# TOP.net
KiCad netlist of a schematic drawn in Altium Designer
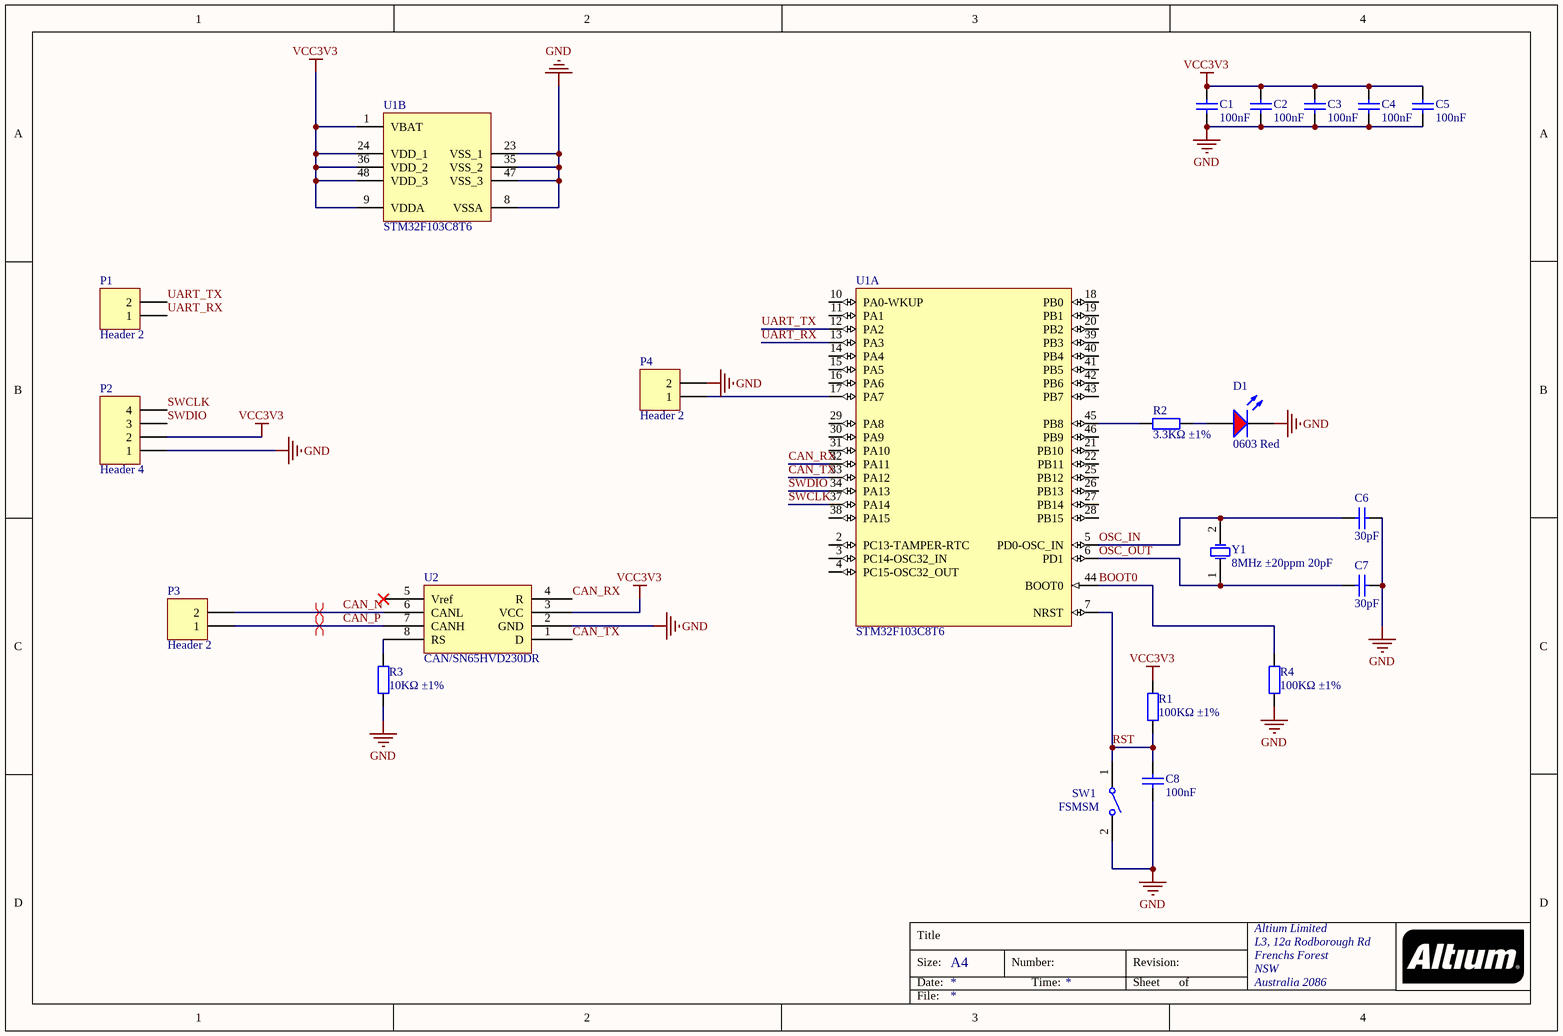
[diagram p0: TOP.SchDoc]

(export (version "E")
  (design (tool "Eeschema 10.0.6"))
  (components
    (comp (ref "C1")
      (value "100nF")
      (footprint "0402_C")
      (description "Chip capacitors")
      (fields
        (field (name "MANUFACTURER") "Samsung Electro-Mechanics")
        (field (name "PARTNUMBER") "CL05B104KO5NNNC")
      )
      (libsource (lib "Miscellaneous Devices LC") (part "0402 100nF (104) 10% 16V"))
    )
    (comp (ref "C2")
      (value "100nF")
      (footprint "0402_C")
      (description "Chip capacitors")
      (fields
        (field (name "MANUFACTURER") "Samsung Electro-Mechanics")
        (field (name "PARTNUMBER") "CL05B104KO5NNNC")
      )
      (libsource (lib "Miscellaneous Devices LC") (part "0402 100nF (104) 10% 16V"))
    )
    (comp (ref "C3")
      (value "100nF")
      (footprint "0402_C")
      (description "Chip capacitors")
      (fields
        (field (name "MANUFACTURER") "Samsung Electro-Mechanics")
        (field (name "PARTNUMBER") "CL05B104KO5NNNC")
      )
      (libsource (lib "Miscellaneous Devices LC") (part "0402 100nF (104) 10% 16V"))
    )
    (comp (ref "C4")
      (value "100nF")
      (footprint "0402_C")
      (description "Chip capacitors")
      (fields
        (field (name "MANUFACTURER") "Samsung Electro-Mechanics")
        (field (name "PARTNUMBER") "CL05B104KO5NNNC")
      )
      (libsource (lib "Miscellaneous Devices LC") (part "0402 100nF (104) 10% 16V"))
    )
    (comp (ref "C5")
      (value "100nF")
      (footprint "0402_C")
      (description "Chip capacitors")
      (fields
        (field (name "MANUFACTURER") "Samsung Electro-Mechanics")
        (field (name "PARTNUMBER") "CL05B104KO5NNNC")
      )
      (libsource (lib "Miscellaneous Devices LC") (part "0402 100nF (104) 10% 16V"))
    )
    (comp (ref "C6")
      (value "30pF")
      (footprint "0402_C")
      (description "Chip capacitors")
      (fields
        (field (name "MANUFACTURER") "Guangdong Fenghua Advanced Tech")
        (field (name "PARTNUMBER") "0402CG300J500NT")
      )
      (libsource (lib "Miscellaneous Devices LC") (part "0402 30pF (300) 5% 50V"))
    )
    (comp (ref "C7")
      (value "30pF")
      (footprint "0402_C")
      (description "Chip capacitors")
      (fields
        (field (name "MANUFACTURER") "Guangdong Fenghua Advanced Tech")
        (field (name "PARTNUMBER") "0402CG300J500NT")
      )
      (libsource (lib "Miscellaneous Devices LC") (part "0402 30pF (300) 5% 50V"))
    )
    (comp (ref "C8")
      (value "100nF")
      (footprint "0402_C")
      (description "Chip capacitors")
      (fields
        (field (name "MANUFACTURER") "Samsung Electro-Mechanics")
        (field (name "PARTNUMBER") "CL05B104KO5NNNC")
      )
      (libsource (lib "Miscellaneous Devices LC") (part "0402 100nF (104) 10% 16V"))
    )
    (comp (ref "D1")
      (value "0603 Red")
      (footprint "0603_LED_S1")
      (description "LED")
      (libsource (lib "Miscellaneous Devices LC") (part "0603 LED Red"))
    )
    (comp (ref "P1")
      (value "Header 2")
      (footprint "HDR1X2")
      (description "Header, 2-Pin")
      (fields (field (name "PUBLISHER") "Altium Limited"))
      (libsource (lib "Miscellaneous Connectors") (part "Header 2"))
    )
    (comp (ref "P2")
      (value "Header 4")
      (footprint "HDR1X4")
      (description "Header, 4-Pin")
      (fields (field (name "PUBLISHER") "Altium Limited"))
      (libsource (lib "Miscellaneous Connectors") (part "Header 4"))
    )
    (comp (ref "P3")
      (value "Header 2")
      (footprint "HDR1X2")
      (description "Header, 2-Pin")
      (fields (field (name "PUBLISHER") "Altium Limited"))
      (libsource (lib "Miscellaneous Connectors") (part "Header 2"))
    )
    (comp (ref "P4")
      (value "Header 2")
      (footprint "HDR1X2")
      (description "Header, 2-Pin")
      (fields (field (name "PUBLISHER") "Altium Limited"))
      (libsource (lib "Miscellaneous Connectors") (part "Header 2"))
    )
    (comp (ref "R1")
      (value "100KΩ ±1%")
      (footprint "0402_R")
      (description "Chip resistor")
      (fields (field (name "MANUFACTURER") "Uniroyal Elec") (field (name "PARTNUMBER") "0402WGF1003TCE"))
      (libsource (lib "Miscellaneous Devices LC") (part "0402 100K (1003) 1%"))
    )
    (comp (ref "R2")
      (value "3.3KΩ ±1%")
      (footprint "0402_R")
      (description "Chip resistor")
      (fields (field (name "MANUFACTURER") "Uniroyal Elec") (field (name "PARTNUMBER") "0402WGF3301TCE"))
      (libsource (lib "Miscellaneous Devices LC") (part "0402 3.3K (3301) 1%"))
    )
    (comp (ref "R3")
      (value "10KΩ ±1%")
      (footprint "0402_R")
      (description "Chip resistor")
      (fields (field (name "MANUFACTURER") "Uniroyal Elec") (field (name "PARTNUMBER") "0402WGF1002TCE"))
      (libsource (lib "Miscellaneous Devices LC") (part "0402 10K (1002) 1%"))
    )
    (comp (ref "R4")
      (value "100KΩ ±1%")
      (footprint "0402_R")
      (description "Chip resistor")
      (fields (field (name "MANUFACTURER") "Uniroyal Elec") (field (name "PARTNUMBER") "0402WGF1003TCE"))
      (libsource (lib "Miscellaneous Devices LC") (part "0402 100K (1003) 1%"))
    )
    (comp (ref "SW1")
      (value "FSMSM")
      (footprint "TECO-FSMSM-2_V")
      (description "FSMSM Push Button Switch, 50 mA, -35 to 85 degC, 2-Pin SMD, RoHS, Bulk")
      (fields (field (name "MANUFACTURER") "TE Connectivity"))
      (libsource (lib "Altium Content Vault") (part "SW-SPST-2_C"))
    )
    (comp (ref "U1")
      (value "STM32F103C8T6")
      (footprint "LQFP-48_7x7x05P")
      (description "ARM")
      (libsource (lib "Miscellaneous Devices LC") (part "STM32F103C8T6"))
    )
    (comp (ref "U2")
      (value "CAN/SN65HVD230DR")
      (footprint "SOIC-8_150mil")
      (description "CAN")
      (libsource (lib "Miscellaneous Devices LC") (part "CAN/SN65HVD230DR_[C12084]"))
    )
    (comp (ref "Y1")
      (value "8MHz ±20ppm 20pF")
      (footprint "SMD-5032_2P")
      (description "贴片晶振")
      (libsource (lib "Miscellaneous Devices LC") (part "SMD-5032_2P 8MHz 20ppm 20pF"))
    )
  )
  (nets
    (net (code "1") (name "/BOOT0") (class "Default")
      (node (ref "R4") (pin "2") (pinfunction "2_2") (pintype "passive"))
      (node (ref "U1") (pin "44") (pinfunction "BOOT0_44") (pintype "input"))
    )
    (net (code "2") (name "/CAN_N") (class "Default")
      (node (ref "P3") (pin "2") (pinfunction "2_2") (pintype "passive"))
      (node (ref "U2") (pin "6") (pinfunction "CANL_6") (pintype "passive"))
    )
    (net (code "3") (name "/CAN_P") (class "Default")
      (node (ref "P3") (pin "1") (pinfunction "1_1") (pintype "passive"))
      (node (ref "U2") (pin "7") (pinfunction "CANH_7") (pintype "passive"))
    )
    (net (code "4") (name "/CAN_RX") (class "Default")
      (node (ref "U1") (pin "32") (pinfunction "PA11_32") (pintype "bidirectional"))
      (node (ref "U2") (pin "4") (pinfunction "R_4") (pintype "passive"))
    )
    (net (code "5") (name "/CAN_TX") (class "Default")
      (node (ref "U1") (pin "33") (pinfunction "PA12_33") (pintype "bidirectional"))
      (node (ref "U2") (pin "1") (pinfunction "D_1") (pintype "passive"))
    )
    (net (code "6") (name "/OSC_IN") (class "Default")
      (node (ref "C6") (pin "1") (pinfunction "1_1") (pintype "passive"))
      (node (ref "U1") (pin "5") (pinfunction "PD0-OSC_IN_5") (pintype "bidirectional"))
      (node (ref "Y1") (pin "2") (pinfunction "OSC2_2") (pintype "passive"))
    )
    (net (code "7") (name "/OSC_OUT") (class "Default")
      (node (ref "C7") (pin "1") (pinfunction "1_1") (pintype "passive"))
      (node (ref "U1") (pin "6") (pinfunction "PD1_6") (pintype "bidirectional"))
      (node (ref "Y1") (pin "1") (pinfunction "OSC1_1") (pintype "passive"))
    )
    (net (code "8") (name "/RST") (class "Default")
      (node (ref "C8") (pin "2") (pinfunction "2_2") (pintype "passive"))
      (node (ref "R1") (pin "1") (pinfunction "1_1") (pintype "passive"))
      (node (ref "SW1") (pin "1") (pinfunction "1_1") (pintype "passive"))
      (node (ref "U1") (pin "7") (pinfunction "NRST_7") (pintype "bidirectional"))
    )
    (net (code "9") (name "/SWCLK") (class "Default")
      (node (ref "P2") (pin "4") (pinfunction "4_4") (pintype "passive"))
      (node (ref "U1") (pin "37") (pinfunction "PA14_37") (pintype "bidirectional"))
    )
    (net (code "10") (name "/SWDIO") (class "Default")
      (node (ref "P2") (pin "3") (pinfunction "3_3") (pintype "passive"))
      (node (ref "U1") (pin "34") (pinfunction "PA13_34") (pintype "bidirectional"))
    )
    (net (code "11") (name "/UART_RX") (class "Default")
      (node (ref "P1") (pin "1") (pinfunction "1_1") (pintype "passive"))
      (node (ref "U1") (pin "13") (pinfunction "PA3_13") (pintype "bidirectional"))
    )
    (net (code "12") (name "/UART_TX") (class "Default")
      (node (ref "P1") (pin "2") (pinfunction "2_2") (pintype "passive"))
      (node (ref "U1") (pin "12") (pinfunction "PA2_12") (pintype "bidirectional"))
    )
    (net (code "13") (name "GND") (class "Default")
      (node (ref "C1") (pin "1") (pinfunction "1_1") (pintype "passive"))
      (node (ref "C2") (pin "1") (pinfunction "1_1") (pintype "passive"))
      (node (ref "C3") (pin "1") (pinfunction "1_1") (pintype "passive"))
      (node (ref "C4") (pin "1") (pinfunction "1_1") (pintype "passive"))
      (node (ref "C5") (pin "1") (pinfunction "1_1") (pintype "passive"))
      (node (ref "C6") (pin "2") (pinfunction "2_2") (pintype "passive"))
      (node (ref "C7") (pin "2") (pinfunction "2_2") (pintype "passive"))
      (node (ref "C8") (pin "1") (pinfunction "1_1") (pintype "passive"))
      (node (ref "D1") (pin "K") (pinfunction "K_K") (pintype "passive"))
      (node (ref "P2") (pin "1") (pinfunction "1_1") (pintype "passive"))
      (node (ref "P4") (pin "2") (pinfunction "2_2") (pintype "passive"))
      (node (ref "R3") (pin "1") (pinfunction "1_1") (pintype "passive"))
      (node (ref "R4") (pin "1") (pinfunction "1_1") (pintype "passive"))
      (node (ref "SW1") (pin "2") (pinfunction "2_2") (pintype "passive"))
      (node (ref "U1") (pin "23") (pinfunction "VSS_1_23") (pintype "power_in"))
      (node (ref "U1") (pin "35") (pinfunction "VSS_2_35") (pintype "power_in"))
      (node (ref "U1") (pin "47") (pinfunction "VSS_3_47") (pintype "power_in"))
      (node (ref "U1") (pin "8") (pinfunction "VSSA_8") (pintype "power_in"))
      (node (ref "U2") (pin "2") (pinfunction "GND_2") (pintype "passive"))
    )
    (net (code "14") (name "Net-(D1-PadA)") (class "Default")
      (node (ref "D1") (pin "A") (pinfunction "A_A") (pintype "passive"))
      (node (ref "R2") (pin "2") (pinfunction "2_2") (pintype "passive"))
    )
    (net (code "15") (name "Net-(U1A-PA7)") (class "Default")
      (node (ref "P4") (pin "1") (pinfunction "1_1") (pintype "passive"))
      (node (ref "U1") (pin "17") (pinfunction "PA7_17") (pintype "bidirectional"))
    )
    (net (code "16") (name "Net-(U1A-PB8)") (class "Default")
      (node (ref "R2") (pin "1") (pinfunction "1_1") (pintype "passive"))
      (node (ref "U1") (pin "45") (pinfunction "PB8_45") (pintype "bidirectional"))
    )
    (net (code "17") (name "Net-(U2-RS)") (class "Default")
      (node (ref "R3") (pin "2") (pinfunction "2_2") (pintype "passive"))
      (node (ref "U2") (pin "8") (pinfunction "RS_8") (pintype "passive"))
    )
    (net (code "18") (name "VCC3V3") (class "Default")
      (node (ref "C1") (pin "2") (pinfunction "2_2") (pintype "passive"))
      (node (ref "C2") (pin "2") (pinfunction "2_2") (pintype "passive"))
      (node (ref "C3") (pin "2") (pinfunction "2_2") (pintype "passive"))
      (node (ref "C4") (pin "2") (pinfunction "2_2") (pintype "passive"))
      (node (ref "C5") (pin "2") (pinfunction "2_2") (pintype "passive"))
      (node (ref "P2") (pin "2") (pinfunction "2_2") (pintype "passive"))
      (node (ref "R1") (pin "2") (pinfunction "2_2") (pintype "passive"))
      (node (ref "U1") (pin "1") (pinfunction "VBAT_1") (pintype "power_in"))
      (node (ref "U1") (pin "24") (pinfunction "VDD_1_24") (pintype "power_in"))
      (node (ref "U1") (pin "36") (pinfunction "VDD_2_36") (pintype "power_in"))
      (node (ref "U1") (pin "48") (pinfunction "VDD_3_48") (pintype "power_in"))
      (node (ref "U1") (pin "9") (pinfunction "VDDA_9") (pintype "power_in"))
      (node (ref "U2") (pin "3") (pinfunction "VCC_3") (pintype "passive"))
    )
    (net (code "19") (name "unconnected-(U1A-PA0-WKUP-Pad10)") (class "Default")
      (node (ref "U1") (pin "10") (pinfunction "PA0-WKUP_10") (pintype "bidirectional"))
    )
    (net (code "20") (name "unconnected-(U1A-PA1-Pad11)") (class "Default")
      (node (ref "U1") (pin "11") (pinfunction "PA1_11") (pintype "bidirectional"))
    )
    (net (code "21") (name "unconnected-(U1A-PA4-Pad14)") (class "Default")
      (node (ref "U1") (pin "14") (pinfunction "PA4_14") (pintype "bidirectional"))
    )
    (net (code "22") (name "unconnected-(U1A-PA5-Pad15)") (class "Default")
      (node (ref "U1") (pin "15") (pinfunction "PA5_15") (pintype "bidirectional"))
    )
    (net (code "23") (name "unconnected-(U1A-PA6-Pad16)") (class "Default")
      (node (ref "U1") (pin "16") (pinfunction "PA6_16") (pintype "bidirectional"))
    )
    (net (code "24") (name "unconnected-(U1A-PA8-Pad29)") (class "Default")
      (node (ref "U1") (pin "29") (pinfunction "PA8_29") (pintype "bidirectional"))
    )
    (net (code "25") (name "unconnected-(U1A-PA9-Pad30)") (class "Default")
      (node (ref "U1") (pin "30") (pinfunction "PA9_30") (pintype "bidirectional"))
    )
    (net (code "26") (name "unconnected-(U1A-PA10-Pad31)") (class "Default")
      (node (ref "U1") (pin "31") (pinfunction "PA10_31") (pintype "bidirectional"))
    )
    (net (code "27") (name "unconnected-(U1A-PA15-Pad38)") (class "Default")
      (node (ref "U1") (pin "38") (pinfunction "PA15_38") (pintype "bidirectional"))
    )
    (net (code "28") (name "unconnected-(U1A-PB0-Pad18)") (class "Default")
      (node (ref "U1") (pin "18") (pinfunction "PB0_18") (pintype "bidirectional"))
    )
    (net (code "29") (name "unconnected-(U1A-PB1-Pad19)") (class "Default")
      (node (ref "U1") (pin "19") (pinfunction "PB1_19") (pintype "bidirectional"))
    )
    (net (code "30") (name "unconnected-(U1A-PB2-Pad20)") (class "Default")
      (node (ref "U1") (pin "20") (pinfunction "PB2_20") (pintype "bidirectional"))
    )
    (net (code "31") (name "unconnected-(U1A-PB3-Pad39)") (class "Default")
      (node (ref "U1") (pin "39") (pinfunction "PB3_39") (pintype "bidirectional"))
    )
    (net (code "32") (name "unconnected-(U1A-PB4-Pad40)") (class "Default")
      (node (ref "U1") (pin "40") (pinfunction "PB4_40") (pintype "bidirectional"))
    )
    (net (code "33") (name "unconnected-(U1A-PB5-Pad41)") (class "Default")
      (node (ref "U1") (pin "41") (pinfunction "PB5_41") (pintype "bidirectional"))
    )
    (net (code "34") (name "unconnected-(U1A-PB6-Pad42)") (class "Default")
      (node (ref "U1") (pin "42") (pinfunction "PB6_42") (pintype "bidirectional"))
    )
    (net (code "35") (name "unconnected-(U1A-PB7-Pad43)") (class "Default")
      (node (ref "U1") (pin "43") (pinfunction "PB7_43") (pintype "bidirectional"))
    )
    (net (code "36") (name "unconnected-(U1A-PB9-Pad46)") (class "Default")
      (node (ref "U1") (pin "46") (pinfunction "PB9_46") (pintype "bidirectional"))
    )
    (net (code "37") (name "unconnected-(U1A-PB10-Pad21)") (class "Default")
      (node (ref "U1") (pin "21") (pinfunction "PB10_21") (pintype "bidirectional"))
    )
    (net (code "38") (name "unconnected-(U1A-PB11-Pad22)") (class "Default")
      (node (ref "U1") (pin "22") (pinfunction "PB11_22") (pintype "bidirectional"))
    )
    (net (code "39") (name "unconnected-(U1A-PB12-Pad25)") (class "Default")
      (node (ref "U1") (pin "25") (pinfunction "PB12_25") (pintype "bidirectional"))
    )
    (net (code "40") (name "unconnected-(U1A-PB13-Pad26)") (class "Default")
      (node (ref "U1") (pin "26") (pinfunction "PB13_26") (pintype "bidirectional"))
    )
    (net (code "41") (name "unconnected-(U1A-PB14-Pad27)") (class "Default")
      (node (ref "U1") (pin "27") (pinfunction "PB14_27") (pintype "bidirectional"))
    )
    (net (code "42") (name "unconnected-(U1A-PB15-Pad28)") (class "Default")
      (node (ref "U1") (pin "28") (pinfunction "PB15_28") (pintype "bidirectional"))
    )
    (net (code "43") (name "unconnected-(U1A-PC13-TAMPER-RTC-Pad2)") (class "Default")
      (node (ref "U1") (pin "2") (pinfunction "PC13-TAMPER-RTC_2") (pintype "bidirectional"))
    )
    (net (code "44") (name "unconnected-(U1A-PC14-OSC32_IN-Pad3)") (class "Default")
      (node (ref "U1") (pin "3") (pinfunction "PC14-OSC32_IN_3") (pintype "bidirectional"))
    )
    (net (code "45") (name "unconnected-(U1A-PC15-OSC32_OUT-Pad4)") (class "Default")
      (node (ref "U1") (pin "4") (pinfunction "PC15-OSC32_OUT_4") (pintype "bidirectional"))
    )
    (net (code "46") (name "unconnected-(U2-Vref-Pad5)") (class "Default")
      (node (ref "U2") (pin "5") (pinfunction "Vref_5") (pintype "passive+no_connect"))
    )
  )
)
